# space_charge_psu.net
KiCad netlist of a schematic drawn in EAGLE
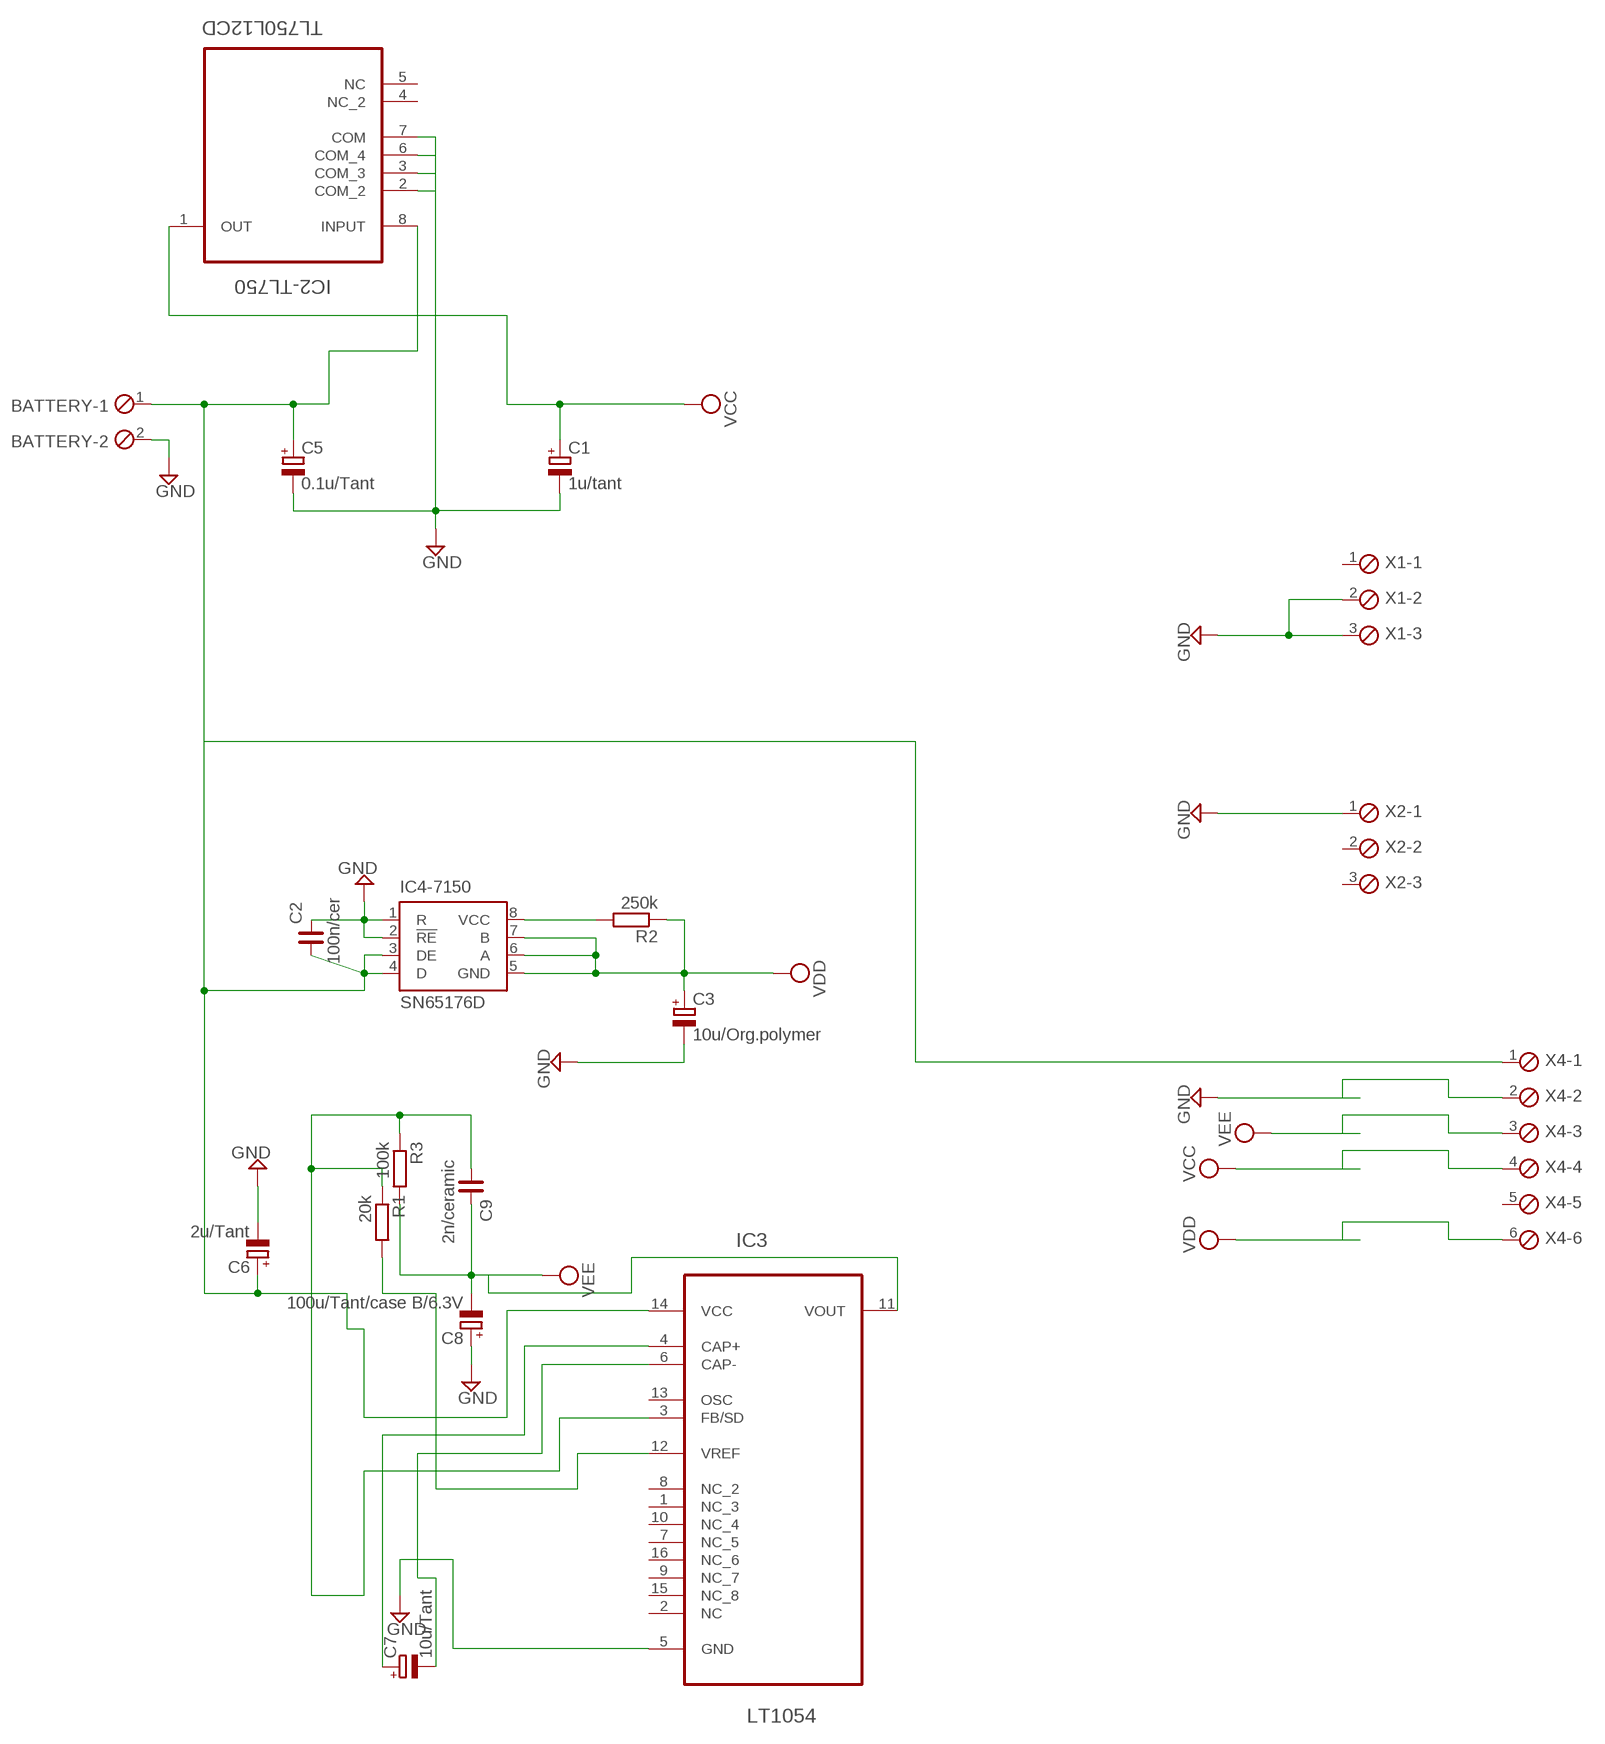
[diagram p0: schematic, sheet 1]

(export (version "E")
  (design (tool "Eeschema 10.0.6"))
  (components
    (comp (ref "BATTERY")
      (value "MPT2")
      (footprint "eagle-import:2POL254")
      (libsource (lib "eagle-import") (part "MPT2"))
    )
    (comp (ref "C1")
      (value "1u/tant")
      (footprint "eagle-import:A_3216-18R")
      (libsource (lib "eagle-import") (part "CPOL-EUA/3216-18R"))
    )
    (comp (ref "C2")
      (value "100n/cer")
      (footprint "eagle-import:C1206")
      (libsource (lib "eagle-import") (part "C_1206"))
    )
    (comp (ref "C3")
      (value "10u/Org.polymer")
      (footprint "eagle-import:153CLV-0505")
      (libsource (lib "eagle-import") (part "CPOL-EU153CLV-0505"))
    )
    (comp (ref "C5")
      (value "0.1u/Tant")
      (footprint "eagle-import:A_3216-18R")
      (libsource (lib "eagle-import") (part "CPOL-EUA/3216-18R"))
    )
    (comp (ref "C6")
      (value "2u/Tant")
      (footprint "eagle-import:A_3216-18R")
      (libsource (lib "eagle-import") (part "CPOL-EUA/3216-18R"))
    )
    (comp (ref "C7")
      (value "10u/Tant")
      (footprint "eagle-import:A_3216-18R")
      (libsource (lib "eagle-import") (part "CPOL-EUA/3216-18R"))
    )
    (comp (ref "C8")
      (value "100u/Tant/case B/6.3V")
      (footprint "eagle-import:B_3528-21R")
      (libsource (lib "eagle-import") (part "CPOL-EUB/3528-21R"))
    )
    (comp (ref "C9")
      (value "2n/ceramic")
      (footprint "eagle-import:C1206")
      (libsource (lib "eagle-import") (part "C_1206"))
    )
    (comp (ref "IC2-TL750")
      (value "TL750L12CD")
      (footprint "eagle-import:SOIC127P600X175-8N")
      (libsource (lib "eagle-import") (part "TL750L12CD"))
    )
    (comp (ref "IC3")
      (value "LT1054")
      (footprint "eagle-import:SOIC127P1030X265-16N")
      (fields (field (name "MPN") "LT1054CDW"))
      (libsource (lib "eagle-import") (part "LT1054CDW"))
    )
    (comp (ref "IC4-7150")
      (value "SN65176D")
      (footprint "eagle-import:SO-08")
      (fields (field (name "MF") "TEXAS INSTRUMENTS") (field (name "MPN") "SN65176BD"))
      (libsource (lib "eagle-import") (part "SN65176D"))
    )
    (comp (ref "R1")
      (value "20k")
      (footprint "eagle-import:R1206")
      (libsource (lib "eagle-import") (part "R-EU_R1206"))
    )
    (comp (ref "R2")
      (value "250k")
      (footprint "eagle-import:R1206")
      (libsource (lib "eagle-import") (part "R-EU_R1206"))
    )
    (comp (ref "R3")
      (value "100k")
      (footprint "eagle-import:R1206")
      (libsource (lib "eagle-import") (part "R-EU_R1206"))
    )
    (comp (ref "X1")
      (value "MPT3")
      (footprint "eagle-import:3POL254")
      (libsource (lib "eagle-import") (part "MPT3"))
    )
    (comp (ref "X2")
      (value "MPT3")
      (footprint "eagle-import:3POL254")
      (libsource (lib "eagle-import") (part "MPT3"))
    )
    (comp (ref "X4")
      (value "MPT6")
      (footprint "eagle-import:6POL254")
      (libsource (lib "eagle-import") (part "MPT6"))
    )
  )
  (nets
    (net (code "1") (name "GND") (class "Default")
      (node (ref "BATTERY") (pin "2") (pinfunction "1_2") (pintype "passive"))
      (node (ref "C1") (pin "-") (pinfunction "-_-") (pintype "passive"))
      (node (ref "C2") (pin "2") (pinfunction "2_2") (pintype "passive"))
      (node (ref "C3") (pin "-") (pinfunction "-_-") (pintype "passive"))
      (node (ref "C5") (pin "-") (pinfunction "-_-") (pintype "passive"))
      (node (ref "C6") (pin "-") (pinfunction "-_-") (pintype "passive"))
      (node (ref "C8") (pin "+") (pinfunction "+_+") (pintype "passive"))
      (node (ref "IC2-TL750") (pin "2") (pinfunction "COM_2_2") (pintype "passive"))
      (node (ref "IC2-TL750") (pin "3") (pinfunction "COM_3_3") (pintype "passive"))
      (node (ref "IC2-TL750") (pin "6") (pinfunction "COM_4_6") (pintype "passive"))
      (node (ref "IC2-TL750") (pin "7") (pinfunction "COM_7") (pintype "passive"))
      (node (ref "IC3") (pin "5") (pinfunction "GND_5") (pintype "passive"))
      (node (ref "IC4-7150") (pin "1") (pinfunction "R_1") (pintype "input"))
      (node (ref "IC4-7150") (pin "2") (pinfunction "~{RE}_2") (pintype "input"))
      (node (ref "X1") (pin "2") (pinfunction "1_2") (pintype "passive"))
      (node (ref "X1") (pin "3") (pinfunction "1_3") (pintype "passive"))
      (node (ref "X2") (pin "1") (pinfunction "1_1") (pintype "passive"))
      (node (ref "X4") (pin "2") (pinfunction "1_2") (pintype "passive"))
    )
    (net (code "2") (name "Net-(IC2-TL750-INPUT)") (class "Default")
      (node (ref "BATTERY") (pin "1") (pinfunction "1_1") (pintype "passive"))
      (node (ref "C2") (pin "1") (pinfunction "1_1") (pintype "passive"))
      (node (ref "C5") (pin "+") (pinfunction "+_+") (pintype "passive"))
      (node (ref "C6") (pin "+") (pinfunction "+_+") (pintype "passive"))
      (node (ref "IC2-TL750") (pin "8") (pinfunction "INPUT_8") (pintype "input"))
      (node (ref "IC3") (pin "14") (pinfunction "VCC_14") (pintype "power_in"))
      (node (ref "IC4-7150") (pin "3") (pinfunction "DE_3") (pintype "input"))
      (node (ref "IC4-7150") (pin "4") (pinfunction "D_4") (pintype "input"))
      (node (ref "X4") (pin "1") (pinfunction "1_1") (pintype "passive"))
    )
    (net (code "3") (name "Net-(IC3-CAP+)") (class "Default")
      (node (ref "C7") (pin "+") (pinfunction "+_+") (pintype "passive"))
      (node (ref "IC3") (pin "4") (pinfunction "CAP+_4") (pintype "input"))
    )
    (net (code "4") (name "Net-(IC3-CAP-)") (class "Default")
      (node (ref "C7") (pin "-") (pinfunction "-_-") (pintype "passive"))
      (node (ref "IC3") (pin "6") (pinfunction "CAP-_6") (pintype "input"))
    )
    (net (code "5") (name "Net-(IC3-FB{slash}SD)") (class "Default")
      (node (ref "C9") (pin "1") (pinfunction "1_1") (pintype "passive"))
      (node (ref "IC3") (pin "3") (pinfunction "FB/SD_3") (pintype "input"))
      (node (ref "R1") (pin "1") (pinfunction "1_1") (pintype "passive"))
      (node (ref "R3") (pin "1") (pinfunction "1_1") (pintype "passive"))
    )
    (net (code "6") (name "Net-(IC3-VREF)") (class "Default")
      (node (ref "IC3") (pin "12") (pinfunction "VREF_12") (pintype "input"))
      (node (ref "R1") (pin "2") (pinfunction "2_2") (pintype "passive"))
    )
    (net (code "7") (name "Net-(IC4-7150-VCC)") (class "Default")
      (node (ref "IC4-7150") (pin "8") (pinfunction "VCC_8") (pintype "input"))
      (node (ref "R2") (pin "2") (pinfunction "2_2") (pintype "passive"))
    )
    (net (code "8") (name "VCC") (class "Default")
      (node (ref "C1") (pin "+") (pinfunction "+_+") (pintype "passive"))
      (node (ref "IC2-TL750") (pin "1") (pinfunction "OUT_1") (pintype "output"))
      (node (ref "X4") (pin "4") (pinfunction "1_4") (pintype "passive"))
    )
    (net (code "9") (name "VDD") (class "Default")
      (node (ref "C3") (pin "+") (pinfunction "+_+") (pintype "passive"))
      (node (ref "IC4-7150") (pin "5") (pinfunction "GND_5") (pintype "input"))
      (node (ref "IC4-7150") (pin "6") (pinfunction "A_6") (pintype "input"))
      (node (ref "IC4-7150") (pin "7") (pinfunction "B_7") (pintype "input"))
      (node (ref "R2") (pin "1") (pinfunction "1_1") (pintype "passive"))
      (node (ref "X4") (pin "6") (pinfunction "1_6") (pintype "passive"))
    )
    (net (code "10") (name "VEE") (class "Default")
      (node (ref "C8") (pin "-") (pinfunction "-_-") (pintype "passive"))
      (node (ref "C9") (pin "2") (pinfunction "2_2") (pintype "passive"))
      (node (ref "IC3") (pin "11") (pinfunction "VOUT_11") (pintype "output"))
      (node (ref "R3") (pin "2") (pinfunction "2_2") (pintype "passive"))
      (node (ref "X4") (pin "3") (pinfunction "1_3") (pintype "passive"))
    )
    (net (code "11") (name "unconnected-(IC2-TL750-NC-Pad5)") (class "Default")
      (node (ref "IC2-TL750") (pin "5") (pinfunction "NC_5") (pintype "no_connect"))
    )
    (net (code "12") (name "unconnected-(IC2-TL750-NC_2-Pad4)") (class "Default")
      (node (ref "IC2-TL750") (pin "4") (pinfunction "NC_2_4") (pintype "no_connect"))
    )
    (net (code "13") (name "unconnected-(IC3-NC-Pad2)") (class "Default")
      (node (ref "IC3") (pin "2") (pinfunction "NC_2") (pintype "no_connect"))
    )
    (net (code "14") (name "unconnected-(IC3-NC_2-Pad8)") (class "Default")
      (node (ref "IC3") (pin "8") (pinfunction "NC_2_8") (pintype "no_connect"))
    )
    (net (code "15") (name "unconnected-(IC3-NC_3-Pad1)") (class "Default")
      (node (ref "IC3") (pin "1") (pinfunction "NC_3_1") (pintype "no_connect"))
    )
    (net (code "16") (name "unconnected-(IC3-NC_4-Pad10)") (class "Default")
      (node (ref "IC3") (pin "10") (pinfunction "NC_4_10") (pintype "no_connect"))
    )
    (net (code "17") (name "unconnected-(IC3-NC_5-Pad7)") (class "Default")
      (node (ref "IC3") (pin "7") (pinfunction "NC_5_7") (pintype "no_connect"))
    )
    (net (code "18") (name "unconnected-(IC3-NC_6-Pad16)") (class "Default")
      (node (ref "IC3") (pin "16") (pinfunction "NC_6_16") (pintype "no_connect"))
    )
    (net (code "19") (name "unconnected-(IC3-NC_7-Pad9)") (class "Default")
      (node (ref "IC3") (pin "9") (pinfunction "NC_7_9") (pintype "no_connect"))
    )
    (net (code "20") (name "unconnected-(IC3-NC_8-Pad15)") (class "Default")
      (node (ref "IC3") (pin "15") (pinfunction "NC_8_15") (pintype "no_connect"))
    )
    (net (code "21") (name "unconnected-(IC3-OSC-Pad13)") (class "Default")
      (node (ref "IC3") (pin "13") (pinfunction "OSC_13") (pintype "input"))
    )
    (net (code "22") (name "unconnected-(X1-Pad1)") (class "Default")
      (node (ref "X1") (pin "1") (pinfunction "1_1") (pintype "passive"))
    )
    (net (code "23") (name "unconnected-(X2B-1-Pad2)") (class "Default")
      (node (ref "X2") (pin "2") (pinfunction "1_2") (pintype "passive"))
    )
    (net (code "24") (name "unconnected-(X2C-1-Pad3)") (class "Default")
      (node (ref "X2") (pin "3") (pinfunction "1_3") (pintype "passive"))
    )
    (net (code "25") (name "unconnected-(X4E-1-Pad5)") (class "Default")
      (node (ref "X4") (pin "5") (pinfunction "1_5") (pintype "passive"))
    )
  )
)
